# 5G8_fpv_tx.net
KiCad netlist of a schematic drawn in EAGLE
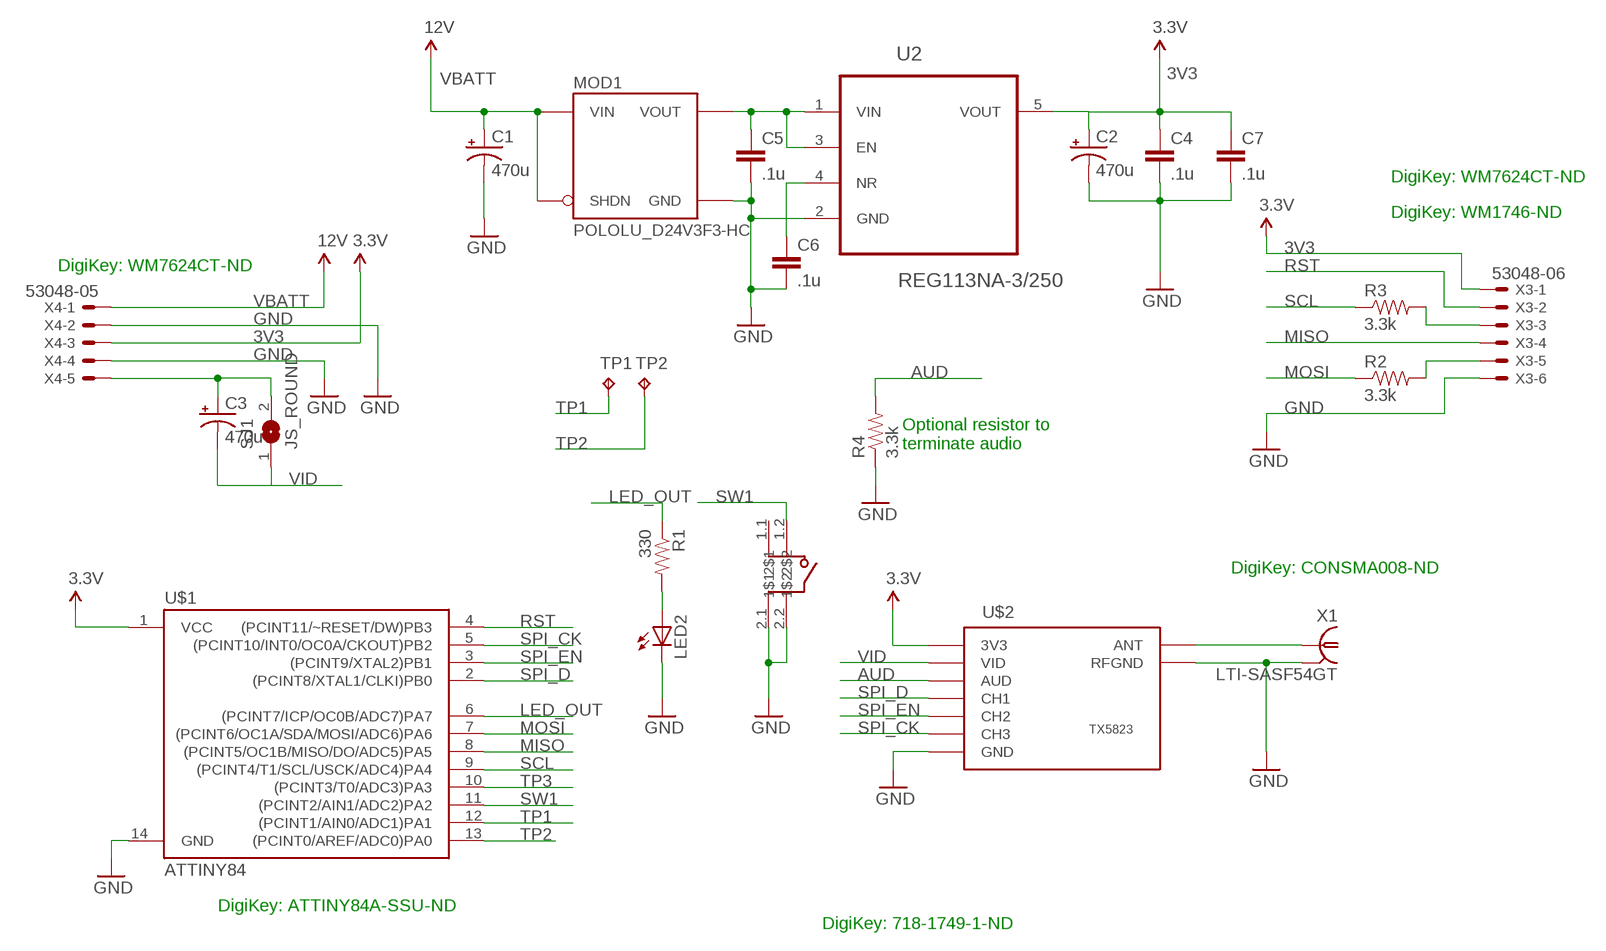
[diagram p0: schematic, sheet 1]

(export (version "E")
  (design (tool "Eeschema 10.0.6"))
  (components
    (comp (ref "C1")
      (value "470u")
      (footprint "eagle-import:VISHAY_D")
      (libsource (lib "eagle-import") (part "VISHAY_D"))
    )
    (comp (ref "C2")
      (value "470u")
      (footprint "eagle-import:VISHAY_D")
      (libsource (lib "eagle-import") (part "VISHAY_D"))
    )
    (comp (ref "C3")
      (value "470u")
      (footprint "eagle-import:VISHAY_D")
      (libsource (lib "eagle-import") (part "VISHAY_D"))
    )
    (comp (ref "C4")
      (value ".1u")
      (footprint "eagle-import:0805")
      (libsource (lib "eagle-import") (part "CAP0805"))
    )
    (comp (ref "C5")
      (value ".1u")
      (footprint "eagle-import:0805")
      (libsource (lib "eagle-import") (part "CAP0805"))
    )
    (comp (ref "C6")
      (value ".1u")
      (footprint "eagle-import:0805")
      (libsource (lib "eagle-import") (part "CAP0805"))
    )
    (comp (ref "C7")
      (value ".1u")
      (footprint "eagle-import:0805")
      (libsource (lib "eagle-import") (part "CAP0805"))
    )
    (comp (ref "LED2")
      (value "LEDCHIPLED_0805")
      (footprint "eagle-import:CHIPLED_0805")
      (libsource (lib "eagle-import") (part "LEDCHIPLED_0805"))
    )
    (comp (ref "MOD1")
      (value "POLOLU_D24V3F3-HC")
      (footprint "eagle-import:POLOLU_D24V3F_HC")
      (libsource (lib "eagle-import") (part "POLOLU_D24V3F-HC3"))
    )
    (comp (ref "R1")
      (value "330")
      (footprint "eagle-import:0805")
      (libsource (lib "eagle-import") (part "RESISTOR0805-RES"))
    )
    (comp (ref "R2")
      (value "3.3k")
      (footprint "eagle-import:0805")
      (libsource (lib "eagle-import") (part "RESISTOR0805-RES"))
    )
    (comp (ref "R3")
      (value "3.3k")
      (footprint "eagle-import:0805")
      (libsource (lib "eagle-import") (part "RESISTOR0805-RES"))
    )
    (comp (ref "R4")
      (value "3.3k")
      (footprint "eagle-import:0805")
      (libsource (lib "eagle-import") (part "RESISTOR0805-RES"))
    )
    (comp (ref "SJ1")
      (value "JS_ROUND")
      (footprint "eagle-import:SJ_ROUND")
      (libsource (lib "eagle-import") (part "JS_ROUND"))
    )
    (comp (ref "TP1")
      (value "TPTP06SQ")
      (footprint "eagle-import:TP06SQ")
      (libsource (lib "eagle-import") (part "TPTP06SQ"))
    )
    (comp (ref "TP2")
      (value "TPTP06SQ")
      (footprint "eagle-import:TP06SQ")
      (libsource (lib "eagle-import") (part "TPTP06SQ"))
    )
    (comp (ref "U$1")
      (value "ATTINY84")
      (footprint "eagle-import:SO14")
      (libsource (lib "eagle-import") (part "ATTINY84"))
    )
    (comp (ref "U$2")
      (value "TX5823")
      (footprint "eagle-import:TX5823")
      (libsource (lib "eagle-import") (part "TX5823"))
    )
    (comp (ref "U$3")
      (value "BOURNS_7814G_SW")
      (footprint "eagle-import:7914G")
      (libsource (lib "eagle-import") (part "BOURNS_7814G_SW"))
    )
    (comp (ref "U2")
      (value "REG113NA-3/250")
      (footprint "eagle-import:SOT95P280X145-5N")
      (libsource (lib "eagle-import") (part "REG113NA-3/250"))
    )
    (comp (ref "X1")
      (value "LTI-SASF54GT")
      (footprint "eagle-import:LTI-SASF54GT")
      (libsource (lib "eagle-import") (part "LTI-SASF54GT"))
    )
    (comp (ref "X3")
      (value "53048-06")
      (footprint "eagle-import:53048-06")
      (fields (field (name "MF") "WALDOM/MOLEX") (field (name "MPN") "53048-0610"))
      (libsource (lib "eagle-import") (part "53?-06048"))
    )
    (comp (ref "X4")
      (value "53048-05")
      (footprint "eagle-import:53048-05")
      (fields (field (name "MF") "MOLEX") (field (name "MPN") "53048-0510"))
      (libsource (lib "eagle-import") (part "53?-05048"))
    )
  )
  (nets
    (net (code "1") (name "/AUD") (class "Default")
      (node (ref "R4") (pin "2") (pinfunction "2_2") (pintype "passive"))
      (node (ref "U$2") (pin "P$2") (pinfunction "AUD_P$2") (pintype "bidirectional"))
    )
    (net (code "2") (name "/LED_OUT") (class "Default")
      (node (ref "R1") (pin "1") (pinfunction "1_1") (pintype "passive"))
      (node (ref "U$1") (pin "6") (pinfunction "(PCINT7/ICP/OC0B/ADC7)PA7_6") (pintype "bidirectional"))
    )
    (net (code "3") (name "/MISO") (class "Default")
      (node (ref "U$1") (pin "8") (pinfunction "(PCINT5/OC1B/MISO/DO/ADC5)PA5_8") (pintype "bidirectional"))
      (node (ref "X3") (pin "4") (pinfunction "S_4") (pintype "passive"))
    )
    (net (code "4") (name "/MOSI") (class "Default")
      (node (ref "R2") (pin "1") (pinfunction "1_1") (pintype "passive"))
      (node (ref "U$1") (pin "7") (pinfunction "(PCINT6/OC1A/SDA/MOSI/ADC6)PA6_7") (pintype "bidirectional"))
    )
    (net (code "5") (name "/RST") (class "Default")
      (node (ref "U$1") (pin "4") (pinfunction "(PCINT11/~{RESET/DW})PB3_4") (pintype "bidirectional"))
      (node (ref "X3") (pin "2") (pinfunction "S_2") (pintype "passive"))
    )
    (net (code "6") (name "/SCL") (class "Default")
      (node (ref "R3") (pin "1") (pinfunction "1_1") (pintype "passive"))
      (node (ref "U$1") (pin "9") (pinfunction "(PCINT4/T1/SCL/USCK/ADC4)PA4_9") (pintype "bidirectional"))
    )
    (net (code "7") (name "/SPI_CK") (class "Default")
      (node (ref "U$1") (pin "5") (pinfunction "(PCINT10/INT0/OC0A/CKOUT)PB2_5") (pintype "bidirectional"))
      (node (ref "U$2") (pin "P$8") (pinfunction "CH3_P$8") (pintype "bidirectional"))
    )
    (net (code "8") (name "/SPI_D") (class "Default")
      (node (ref "U$1") (pin "2") (pinfunction "(PCINT8/XTAL1/CLKI)PB0_2") (pintype "bidirectional"))
      (node (ref "U$2") (pin "P$6") (pinfunction "CH1_P$6") (pintype "bidirectional"))
    )
    (net (code "9") (name "/SPI_EN") (class "Default")
      (node (ref "U$1") (pin "3") (pinfunction "(PCINT9/XTAL2)PB1_3") (pintype "bidirectional"))
      (node (ref "U$2") (pin "P$7") (pinfunction "CH2_P$7") (pintype "bidirectional"))
    )
    (net (code "10") (name "/SW1") (class "Default")
      (node (ref "U$1") (pin "11") (pinfunction "(PCINT2/AIN1/ADC2)PA2_11") (pintype "bidirectional"))
      (node (ref "U$3") (pin "1.2") (pinfunction "1$2_1.2") (pintype "bidirectional"))
    )
    (net (code "11") (name "/TP1") (class "Default")
      (node (ref "TP1") (pin "TP") (pinfunction "TP_TP") (pintype "input"))
      (node (ref "U$1") (pin "12") (pinfunction "(PCINT1/AIN0/ADC1)PA1_12") (pintype "bidirectional"))
    )
    (net (code "12") (name "/TP2") (class "Default")
      (node (ref "TP2") (pin "TP") (pinfunction "TP_TP") (pintype "input"))
      (node (ref "U$1") (pin "13") (pinfunction "(PCINT0/AREF/ADC0)PA0_13") (pintype "bidirectional"))
    )
    (net (code "13") (name "/TP3") (class "Default")
      (node (ref "U$1") (pin "10") (pinfunction "(PCINT3/T0/ADC3)PA3_10") (pintype "bidirectional"))
    )
    (net (code "14") (name "/VID") (class "Default")
      (node (ref "C3") (pin "-") (pinfunction "-_-") (pintype "passive"))
      (node (ref "SJ1") (pin "1") (pinfunction "1_1") (pintype "passive"))
      (node (ref "U$2") (pin "P$1") (pinfunction "VID_P$1") (pintype "bidirectional"))
    )
    (net (code "15") (name "3.3V") (class "Default")
      (node (ref "C2") (pin "+") (pinfunction "+_+") (pintype "passive"))
      (node (ref "C4") (pin "1") (pinfunction "1_1") (pintype "passive"))
      (node (ref "C7") (pin "1") (pinfunction "1_1") (pintype "passive"))
      (node (ref "U$1") (pin "1") (pinfunction "VCC_1") (pintype "bidirectional"))
      (node (ref "U$2") (pin "P$4") (pinfunction "3V3_P$4") (pintype "bidirectional"))
      (node (ref "U2") (pin "5") (pinfunction "VOUT_5") (pintype "output"))
      (node (ref "X3") (pin "1") (pinfunction "S_1") (pintype "passive"))
      (node (ref "X4") (pin "3") (pinfunction "S_3") (pintype "passive"))
    )
    (net (code "16") (name "12V") (class "Default")
      (node (ref "C1") (pin "+") (pinfunction "+_+") (pintype "passive"))
      (node (ref "MOD1") (pin "I") (pinfunction "VIN_I") (pintype "power_in"))
      (node (ref "MOD1") (pin "S") (pinfunction "SHDN_S") (pintype "input"))
      (node (ref "X4") (pin "1") (pinfunction "S_1") (pintype "passive"))
    )
    (net (code "17") (name "GND") (class "Default")
      (node (ref "C1") (pin "-") (pinfunction "-_-") (pintype "passive"))
      (node (ref "C2") (pin "-") (pinfunction "-_-") (pintype "passive"))
      (node (ref "C4") (pin "2") (pinfunction "2_2") (pintype "passive"))
      (node (ref "C5") (pin "2") (pinfunction "2_2") (pintype "passive"))
      (node (ref "C6") (pin "2") (pinfunction "2_2") (pintype "passive"))
      (node (ref "C7") (pin "2") (pinfunction "2_2") (pintype "passive"))
      (node (ref "LED2") (pin "C") (pinfunction "C_C") (pintype "passive"))
      (node (ref "MOD1") (pin "G") (pinfunction "GND_G") (pintype "power_in"))
      (node (ref "R4") (pin "1") (pinfunction "1_1") (pintype "passive"))
      (node (ref "U$1") (pin "14") (pinfunction "GND_14") (pintype "bidirectional"))
      (node (ref "U$2") (pin "P$11") (pinfunction "RFGND_P$11") (pintype "bidirectional"))
      (node (ref "U$2") (pin "P$3") (pinfunction "GND_P$3") (pintype "bidirectional"))
      (node (ref "U$2") (pin "P$5") (pinfunction "GND_P$5") (pintype "bidirectional"))
      (node (ref "U$2") (pin "P$9") (pinfunction "RFGND_P$9") (pintype "bidirectional"))
      (node (ref "U$3") (pin "2.1") (pinfunction "2$1_2.1") (pintype "bidirectional"))
      (node (ref "U$3") (pin "2.2") (pinfunction "2$2_2.2") (pintype "bidirectional"))
      (node (ref "U2") (pin "2") (pinfunction "GND_2") (pintype "passive"))
      (node (ref "X1") (pin "2") (pinfunction "2_2") (pintype "passive"))
      (node (ref "X1") (pin "3") (pinfunction "2_3") (pintype "passive"))
      (node (ref "X1") (pin "4") (pinfunction "2_4") (pintype "passive"))
      (node (ref "X1") (pin "5") (pinfunction "2_5") (pintype "passive"))
      (node (ref "X3") (pin "6") (pinfunction "S_6") (pintype "passive"))
      (node (ref "X4") (pin "2") (pinfunction "S_2") (pintype "passive"))
      (node (ref "X4") (pin "4") (pinfunction "S_4") (pintype "passive"))
    )
    (net (code "18") (name "Net-(LED2-PadA)") (class "Default")
      (node (ref "LED2") (pin "A") (pinfunction "A_A") (pintype "passive"))
      (node (ref "R1") (pin "2") (pinfunction "2_2") (pintype "passive"))
    )
    (net (code "19") (name "Net-(MOD1-VOUT)") (class "Default")
      (node (ref "C5") (pin "1") (pinfunction "1_1") (pintype "passive"))
      (node (ref "MOD1") (pin "O") (pinfunction "VOUT_O") (pintype "output"))
      (node (ref "U2") (pin "1") (pinfunction "VIN_1") (pintype "power_in"))
      (node (ref "U2") (pin "3") (pinfunction "EN_3") (pintype "input"))
    )
    (net (code "20") (name "Net-(U$2-ANT)") (class "Default")
      (node (ref "U$2") (pin "P$10") (pinfunction "ANT_P$10") (pintype "bidirectional"))
      (node (ref "X1") (pin "1") (pinfunction "1_1") (pintype "passive"))
    )
    (net (code "21") (name "Net-(U2-NR)") (class "Default")
      (node (ref "C6") (pin "1") (pinfunction "1_1") (pintype "passive"))
      (node (ref "U2") (pin "4") (pinfunction "NR_4") (pintype "input"))
    )
    (net (code "22") (name "Net-(X3C-S)") (class "Default")
      (node (ref "R3") (pin "2") (pinfunction "2_2") (pintype "passive"))
      (node (ref "X3") (pin "3") (pinfunction "S_3") (pintype "passive"))
    )
    (net (code "23") (name "Net-(X3E-S)") (class "Default")
      (node (ref "R2") (pin "2") (pinfunction "2_2") (pintype "passive"))
      (node (ref "X3") (pin "5") (pinfunction "S_5") (pintype "passive"))
    )
    (net (code "24") (name "Net-(X4E-S)") (class "Default")
      (node (ref "C3") (pin "+") (pinfunction "+_+") (pintype "passive"))
      (node (ref "SJ1") (pin "2") (pinfunction "2_2") (pintype "passive"))
      (node (ref "X4") (pin "5") (pinfunction "S_5") (pintype "passive"))
    )
    (net (code "25") (name "unconnected-(U$3-1$1-Pad1.1)") (class "Default")
      (node (ref "U$3") (pin "1.1") (pinfunction "1$1_1.1") (pintype "bidirectional"))
    )
  )
)
